# Schaltplan1.net
KiCad netlist of a schematic drawn in EAGLE
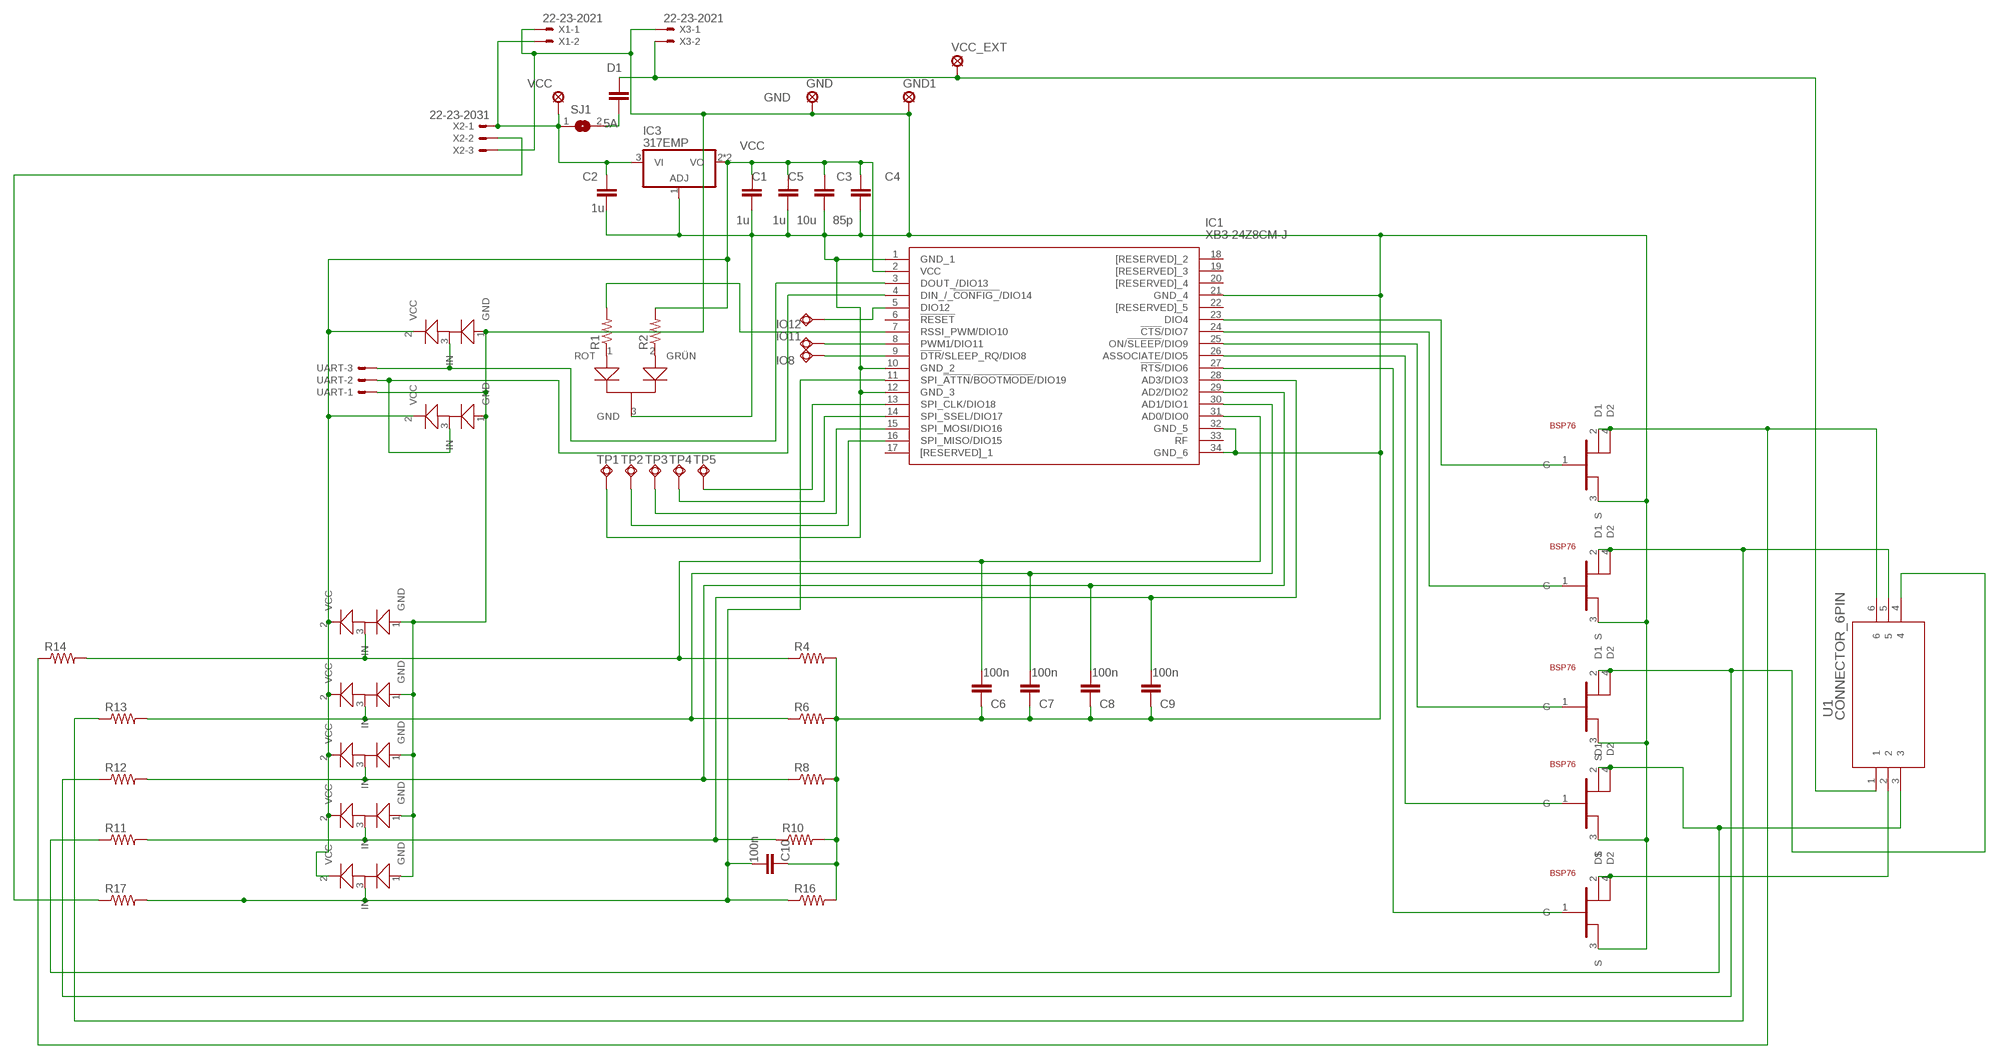
[diagram p0: schematic, sheet 1]

(export (version "E")
  (design (tool "Eeschema 10.0.6"))
  (components
    (comp (ref "C1")
      (value "1u")
      (footprint "eagle-import:CAP_0805")
      (fields
        (field (name "DIGIKEY_PART_NUMBER") "311-1140-2-ND")
        (field (name "MANUFACTURER") "Yageo")
        (field (name "MPN") "CC0805KRX7R9BB104")
        (field (name "CREATED_BY") "PCBLayout.com")
      )
      (libsource (lib "eagle-import") (part "CC0805KRX7R9BB104"))
    )
    (comp (ref "C2")
      (value "1u")
      (footprint "eagle-import:CAP_0805")
      (fields
        (field (name "DIGIKEY_PART_NUMBER") "311-1140-2-ND")
        (field (name "MANUFACTURER") "Yageo")
        (field (name "MPN") "CC0805KRX7R9BB104")
        (field (name "CREATED_BY") "PCBLayout.com")
      )
      (libsource (lib "eagle-import") (part "CC0805KRX7R9BB104"))
    )
    (comp (ref "C3")
      (value "10u")
      (footprint "eagle-import:CAP_0805")
      (fields
        (field (name "DIGIKEY_PART_NUMBER") "311-1140-2-ND")
        (field (name "MANUFACTURER") "Yageo")
        (field (name "MPN") "CC0805KRX7R9BB104")
        (field (name "CREATED_BY") "PCBLayout.com")
      )
      (libsource (lib "eagle-import") (part "CC0805KRX7R9BB104"))
    )
    (comp (ref "C4")
      (value "85p")
      (footprint "eagle-import:CAP_0805")
      (fields
        (field (name "DIGIKEY_PART_NUMBER") "311-1140-2-ND")
        (field (name "MANUFACTURER") "Yageo")
        (field (name "MPN") "CC0805KRX7R9BB104")
        (field (name "CREATED_BY") "PCBLayout.com")
      )
      (libsource (lib "eagle-import") (part "CC0805KRX7R9BB104"))
    )
    (comp (ref "C5")
      (value "1u")
      (footprint "eagle-import:CAP_0805")
      (fields
        (field (name "DIGIKEY_PART_NUMBER") "311-1140-2-ND")
        (field (name "MANUFACTURER") "Yageo")
        (field (name "MPN") "CC0805KRX7R9BB104")
        (field (name "CREATED_BY") "PCBLayout.com")
      )
      (libsource (lib "eagle-import") (part "CC0805KRX7R9BB104"))
    )
    (comp (ref "C6")
      (value "100n")
      (footprint "eagle-import:CAP_0805")
      (fields
        (field (name "DIGIKEY_PART_NUMBER") "311-1140-2-ND")
        (field (name "MANUFACTURER") "Yageo")
        (field (name "MPN") "CC0805KRX7R9BB104")
        (field (name "CREATED_BY") "PCBLayout.com")
      )
      (libsource (lib "eagle-import") (part "CC0805KRX7R9BB104"))
    )
    (comp (ref "C7")
      (value "100n")
      (footprint "eagle-import:CAP_0805")
      (fields
        (field (name "DIGIKEY_PART_NUMBER") "311-1140-2-ND")
        (field (name "MANUFACTURER") "Yageo")
        (field (name "MPN") "CC0805KRX7R9BB104")
        (field (name "CREATED_BY") "PCBLayout.com")
      )
      (libsource (lib "eagle-import") (part "CC0805KRX7R9BB104"))
    )
    (comp (ref "C8")
      (value "100n")
      (footprint "eagle-import:CAP_0805")
      (fields
        (field (name "DIGIKEY_PART_NUMBER") "311-1140-2-ND")
        (field (name "MANUFACTURER") "Yageo")
        (field (name "MPN") "CC0805KRX7R9BB104")
        (field (name "CREATED_BY") "PCBLayout.com")
      )
      (libsource (lib "eagle-import") (part "CC0805KRX7R9BB104"))
    )
    (comp (ref "C9")
      (value "100n")
      (footprint "eagle-import:CAP_0805")
      (fields
        (field (name "DIGIKEY_PART_NUMBER") "311-1140-2-ND")
        (field (name "MANUFACTURER") "Yageo")
        (field (name "MPN") "CC0805KRX7R9BB104")
        (field (name "CREATED_BY") "PCBLayout.com")
      )
      (libsource (lib "eagle-import") (part "CC0805KRX7R9BB104"))
    )
    (comp (ref "C10")
      (value "100n")
      (footprint "eagle-import:CAP_0805")
      (fields
        (field (name "DIGIKEY_PART_NUMBER") "311-1140-2-ND")
        (field (name "MANUFACTURER") "Yageo")
        (field (name "MPN") "CC0805KRX7R9BB104")
        (field (name "CREATED_BY") "PCBLayout.com")
      )
      (libsource (lib "eagle-import") (part "CC0805KRX7R9BB104"))
    )
    (comp (ref "D1")
      (value "5A")
      (footprint "eagle-import:CAP_0805")
      (fields
        (field (name "DIGIKEY_PART_NUMBER") "311-1140-2-ND")
        (field (name "MANUFACTURER") "Yageo")
        (field (name "MPN") "CC0805KRX7R9BB104")
        (field (name "CREATED_BY") "PCBLayout.com")
      )
      (libsource (lib "eagle-import") (part "CC0805KRX7R9BB104"))
    )
    (comp (ref "GND")
      (value "LSP10")
      (footprint "eagle-import:LSP10")
      (libsource (lib "eagle-import") (part "LSP10"))
    )
    (comp (ref "GND1")
      (value "LSP10")
      (footprint "eagle-import:LSP10")
      (libsource (lib "eagle-import") (part "LSP10"))
    )
    (comp (ref "IC1")
      (value "XB3-24Z8CM-J")
      (footprint "eagle-import:XB324Z8CMJ")
      (fields (field (name "MOUSER_PART_NUMBER") "888-XB3-24Z8CM-J"))
      (libsource (lib "eagle-import") (part "XB3-24Z8CM-J"))
    )
    (comp (ref "IC3")
      (value "317EMP")
      (footprint "eagle-import:SOT223")
      (libsource (lib "eagle-import") (part "317EMP"))
    )
    (comp (ref "IO8")
      (value "TPSQB1,27")
      (footprint "eagle-import:B1,27")
      (libsource (lib "eagle-import") (part "TPSQB1,27"))
    )
    (comp (ref "IO11")
      (value "TPSQB1,27")
      (footprint "eagle-import:B1,27")
      (libsource (lib "eagle-import") (part "TPSQB1,27"))
    )
    (comp (ref "IO12")
      (value "TPSQB1,27")
      (footprint "eagle-import:B1,27")
      (libsource (lib "eagle-import") (part "TPSQB1,27"))
    )
    (comp (ref "LED")
      (value "LED_RG_SOT23")
      (footprint "eagle-import:SOT23")
      (libsource (lib "eagle-import") (part "LED_RG_SOT23"))
    )
    (comp (ref "R1")
      (value "150")
      (footprint "eagle-import:RES_0805")
      (fields
        (field (name "DIGIKEY_PART_NUMBER") "541-0.0ATR-ND")
        (field (name "MANUFACTURER") "Vishay Dale")
        (field (name "MPN") "CRCW08050000Z0EA")
        (field (name "CREATED_BY") "PCBLayout.com")
      )
      (libsource (lib "eagle-import") (part "CRCW08050000Z0EA"))
    )
    (comp (ref "R2")
      (value "CRCW08050000Z0EA")
      (footprint "eagle-import:RES_0805")
      (fields
        (field (name "DIGIKEY_PART_NUMBER") "541-0.0ATR-ND")
        (field (name "MANUFACTURER") "Vishay Dale")
        (field (name "CREATED_BY") "PCBLayout.com")
      )
      (libsource (lib "eagle-import") (part "CRCW08050000Z0EA"))
    )
    (comp (ref "R4")
      (value "47k")
      (footprint "eagle-import:RES_0805")
      (fields
        (field (name "DIGIKEY_PART_NUMBER") "541-0.0ATR-ND")
        (field (name "MANUFACTURER") "Vishay Dale")
        (field (name "MPN") "CRCW08050000Z0EA")
        (field (name "CREATED_BY") "PCBLayout.com")
      )
      (libsource (lib "eagle-import") (part "CRCW08050000Z0EA"))
    )
    (comp (ref "R6")
      (value "CRCW08050000Z0EA")
      (footprint "eagle-import:RES_0805")
      (fields
        (field (name "DIGIKEY_PART_NUMBER") "541-0.0ATR-ND")
        (field (name "MANUFACTURER") "Vishay Dale")
        (field (name "CREATED_BY") "PCBLayout.com")
      )
      (libsource (lib "eagle-import") (part "CRCW08050000Z0EA"))
    )
    (comp (ref "R8")
      (value "CRCW08050000Z0EA")
      (footprint "eagle-import:RES_0805")
      (fields
        (field (name "DIGIKEY_PART_NUMBER") "541-0.0ATR-ND")
        (field (name "MANUFACTURER") "Vishay Dale")
        (field (name "CREATED_BY") "PCBLayout.com")
      )
      (libsource (lib "eagle-import") (part "CRCW08050000Z0EA"))
    )
    (comp (ref "R10")
      (value "CRCW08050000Z0EA")
      (footprint "eagle-import:RES_0805")
      (fields
        (field (name "DIGIKEY_PART_NUMBER") "541-0.0ATR-ND")
        (field (name "MANUFACTURER") "Vishay Dale")
        (field (name "CREATED_BY") "PCBLayout.com")
      )
      (libsource (lib "eagle-import") (part "CRCW08050000Z0EA"))
    )
    (comp (ref "R11")
      (value "CRCW08050000Z0EA")
      (footprint "eagle-import:RES_0805")
      (fields
        (field (name "DIGIKEY_PART_NUMBER") "541-0.0ATR-ND")
        (field (name "MANUFACTURER") "Vishay Dale")
        (field (name "CREATED_BY") "PCBLayout.com")
      )
      (libsource (lib "eagle-import") (part "CRCW08050000Z0EA"))
    )
    (comp (ref "R12")
      (value "CRCW08050000Z0EA")
      (footprint "eagle-import:RES_0805")
      (fields
        (field (name "DIGIKEY_PART_NUMBER") "541-0.0ATR-ND")
        (field (name "MANUFACTURER") "Vishay Dale")
        (field (name "CREATED_BY") "PCBLayout.com")
      )
      (libsource (lib "eagle-import") (part "CRCW08050000Z0EA"))
    )
    (comp (ref "R13")
      (value "CRCW08050000Z0EA")
      (footprint "eagle-import:RES_0805")
      (fields
        (field (name "DIGIKEY_PART_NUMBER") "541-0.0ATR-ND")
        (field (name "MANUFACTURER") "Vishay Dale")
        (field (name "CREATED_BY") "PCBLayout.com")
      )
      (libsource (lib "eagle-import") (part "CRCW08050000Z0EA"))
    )
    (comp (ref "R14")
      (value "CRCW08050000Z0EA")
      (footprint "eagle-import:RES_0805")
      (fields
        (field (name "DIGIKEY_PART_NUMBER") "541-0.0ATR-ND")
        (field (name "MANUFACTURER") "Vishay Dale")
        (field (name "CREATED_BY") "PCBLayout.com")
      )
      (libsource (lib "eagle-import") (part "CRCW08050000Z0EA"))
    )
    (comp (ref "R16")
      (value "CRCW08050000Z0EA")
      (footprint "eagle-import:RES_0805")
      (fields
        (field (name "DIGIKEY_PART_NUMBER") "541-0.0ATR-ND")
        (field (name "MANUFACTURER") "Vishay Dale")
        (field (name "CREATED_BY") "PCBLayout.com")
      )
      (libsource (lib "eagle-import") (part "CRCW08050000Z0EA"))
    )
    (comp (ref "R17")
      (value "CRCW08050000Z0EA")
      (footprint "eagle-import:RES_0805")
      (fields
        (field (name "DIGIKEY_PART_NUMBER") "541-0.0ATR-ND")
        (field (name "MANUFACTURER") "Vishay Dale")
        (field (name "CREATED_BY") "PCBLayout.com")
      )
      (libsource (lib "eagle-import") (part "CRCW08050000Z0EA"))
    )
    (comp (ref "SJ1")
      (value "SJW")
      (footprint "eagle-import:SJW")
      (libsource (lib "eagle-import") (part "SJW"))
    )
    (comp (ref "TP1")
      (value "TPSQB1,27")
      (footprint "eagle-import:B1,27")
      (libsource (lib "eagle-import") (part "TPSQB1,27"))
    )
    (comp (ref "TP2")
      (value "TPSQB1,27")
      (footprint "eagle-import:B1,27")
      (libsource (lib "eagle-import") (part "TPSQB1,27"))
    )
    (comp (ref "TP3")
      (value "TPSQB1,27")
      (footprint "eagle-import:B1,27")
      (libsource (lib "eagle-import") (part "TPSQB1,27"))
    )
    (comp (ref "TP4")
      (value "TPSQB1,27")
      (footprint "eagle-import:B1,27")
      (libsource (lib "eagle-import") (part "TPSQB1,27"))
    )
    (comp (ref "TP5")
      (value "TPSQB1,27")
      (footprint "eagle-import:B1,27")
      (libsource (lib "eagle-import") (part "TPSQB1,27"))
    )
    (comp (ref "U$1")
      (value "BSP76")
      (footprint "eagle-import:SOT223")
      (libsource (lib "eagle-import") (part "BSP76"))
    )
    (comp (ref "U$2")
      (value "BSP76")
      (footprint "eagle-import:SOT223")
      (libsource (lib "eagle-import") (part "BSP76"))
    )
    (comp (ref "U$3")
      (value "BSP76")
      (footprint "eagle-import:SOT223")
      (libsource (lib "eagle-import") (part "BSP76"))
    )
    (comp (ref "U$4")
      (value "BSP76")
      (footprint "eagle-import:SOT223")
      (libsource (lib "eagle-import") (part "BSP76"))
    )
    (comp (ref "U$5")
      (value "BSP76")
      (footprint "eagle-import:SOT223")
      (libsource (lib "eagle-import") (part "BSP76"))
    )
    (comp (ref "U$6")
      (value "TVS-DIODE")
      (footprint "eagle-import:SOT23-R")
      (libsource (lib "eagle-import") (part "TVS-DIODE"))
    )
    (comp (ref "U$7")
      (value "TVS-DIODE")
      (footprint "eagle-import:SOT23-R")
      (libsource (lib "eagle-import") (part "TVS-DIODE"))
    )
    (comp (ref "U$8")
      (value "TVS-DIODE")
      (footprint "eagle-import:SOT23-R")
      (libsource (lib "eagle-import") (part "TVS-DIODE"))
    )
    (comp (ref "U$9")
      (value "TVS-DIODE")
      (footprint "eagle-import:SOT23-R")
      (libsource (lib "eagle-import") (part "TVS-DIODE"))
    )
    (comp (ref "U$10")
      (value "TVS-DIODE")
      (footprint "eagle-import:SOT23-R")
      (libsource (lib "eagle-import") (part "TVS-DIODE"))
    )
    (comp (ref "U$11")
      (value "TVS-DIODE")
      (footprint "eagle-import:SOT23-R")
      (libsource (lib "eagle-import") (part "TVS-DIODE"))
    )
    (comp (ref "U$12")
      (value "TVS-DIODE")
      (footprint "eagle-import:SOT23-R")
      (libsource (lib "eagle-import") (part "TVS-DIODE"))
    )
    (comp (ref "U1")
      (value "CONNECTOR_6PIN")
      (footprint "eagle-import:282836-6")
      (fields (field (name "MANUFACTURER_PART_NUMBER") "2828366"))
      (libsource (lib "eagle-import") (part "CONNECTOR_6PIN"))
    )
    (comp (ref "UART")
      (value "22-23-2031")
      (footprint "eagle-import:22-23-2031")
      (fields (field (name "MF") "MOLEX"))
      (libsource (lib "eagle-import") (part "22-23-2031"))
    )
    (comp (ref "VCC")
      (value "LSP10")
      (footprint "eagle-import:LSP10")
      (libsource (lib "eagle-import") (part "LSP10"))
    )
    (comp (ref "VCC_EXT")
      (value "LSP10")
      (footprint "eagle-import:LSP10")
      (libsource (lib "eagle-import") (part "LSP10"))
    )
    (comp (ref "X1")
      (value "22-23-2021")
      (footprint "eagle-import:22-23-2021")
      (fields (field (name "MF") "MOLEX"))
      (libsource (lib "eagle-import") (part "22-23-2021"))
    )
    (comp (ref "X2")
      (value "22-23-2031")
      (footprint "eagle-import:22-23-2031")
      (fields (field (name "MF") "MOLEX"))
      (libsource (lib "eagle-import") (part "22-23-2031"))
    )
    (comp (ref "X3")
      (value "22-23-2021")
      (footprint "eagle-import:22-23-2021")
      (fields (field (name "MF") "MOLEX"))
      (libsource (lib "eagle-import") (part "22-23-2021"))
    )
  )
  (nets
    (net (code "1") (name "/GND") (class "Default")
      (node (ref "C1") (pin "2") (pinfunction "2_2") (pintype "passive"))
      (node (ref "C10") (pin "1") (pinfunction "1_1") (pintype "passive"))
      (node (ref "C2") (pin "2") (pinfunction "2_2") (pintype "passive"))
      (node (ref "C3") (pin "1") (pinfunction "1_1") (pintype "passive"))
      (node (ref "C4") (pin "1") (pinfunction "1_1") (pintype "passive"))
      (node (ref "C5") (pin "2") (pinfunction "2_2") (pintype "passive"))
      (node (ref "C6") (pin "1") (pinfunction "1_1") (pintype "passive"))
      (node (ref "C7") (pin "1") (pinfunction "1_1") (pintype "passive"))
      (node (ref "C8") (pin "1") (pinfunction "1_1") (pintype "passive"))
      (node (ref "C9") (pin "1") (pinfunction "1_1") (pintype "passive"))
      (node (ref "GND") (pin "MP") (pinfunction "MP_MP") (pintype "passive"))
      (node (ref "GND1") (pin "MP") (pinfunction "MP_MP") (pintype "passive"))
      (node (ref "IC1") (pin "1") (pinfunction "GND_1_1") (pintype "bidirectional"))
      (node (ref "IC1") (pin "10") (pinfunction "GND_2_10") (pintype "bidirectional"))
      (node (ref "IC1") (pin "12") (pinfunction "GND_3_12") (pintype "bidirectional"))
      (node (ref "IC1") (pin "21") (pinfunction "GND_4_21") (pintype "bidirectional"))
      (node (ref "IC1") (pin "32") (pinfunction "GND_5_32") (pintype "bidirectional"))
      (node (ref "IC1") (pin "34") (pinfunction "GND_6_34") (pintype "bidirectional"))
      (node (ref "IC3") (pin "1") (pinfunction "ADJ_1") (pintype "input"))
      (node (ref "LED") (pin "3") (pinfunction "GND_3") (pintype "bidirectional"))
      (node (ref "R10") (pin "2") (pinfunction "2_2") (pintype "passive"))
      (node (ref "R16") (pin "2") (pinfunction "2_2") (pintype "passive"))
      (node (ref "R4") (pin "2") (pinfunction "2_2") (pintype "passive"))
      (node (ref "R6") (pin "2") (pinfunction "2_2") (pintype "passive"))
      (node (ref "R8") (pin "2") (pinfunction "2_2") (pintype "passive"))
      (node (ref "TP1") (pin "TP") (pinfunction "TP_TP") (pintype "input"))
      (node (ref "U$1") (pin "3") (pinfunction "S_3") (pintype "bidirectional"))
      (node (ref "U$10") (pin "1") (pinfunction "GND_1") (pintype "bidirectional"))
      (node (ref "U$11") (pin "1") (pinfunction "GND_1") (pintype "bidirectional"))
      (node (ref "U$12") (pin "1") (pinfunction "GND_1") (pintype "bidirectional"))
      (node (ref "U$2") (pin "3") (pinfunction "S_3") (pintype "bidirectional"))
      (node (ref "U$3") (pin "3") (pinfunction "S_3") (pintype "bidirectional"))
      (node (ref "U$4") (pin "3") (pinfunction "S_3") (pintype "bidirectional"))
      (node (ref "U$5") (pin "3") (pinfunction "S_3") (pintype "bidirectional"))
      (node (ref "U$6") (pin "1") (pinfunction "GND_1") (pintype "bidirectional"))
      (node (ref "U$7") (pin "1") (pinfunction "GND_1") (pintype "bidirectional"))
      (node (ref "U$8") (pin "1") (pinfunction "GND_1") (pintype "bidirectional"))
      (node (ref "U$9") (pin "1") (pinfunction "GND_1") (pintype "bidirectional"))
      (node (ref "UART") (pin "1") (pinfunction "S_1") (pintype "passive"))
      (node (ref "X1") (pin "1") (pinfunction "S_1") (pintype "passive"))
      (node (ref "X2") (pin "3") (pinfunction "S_3") (pintype "passive"))
      (node (ref "X3") (pin "1") (pinfunction "S_1") (pintype "passive"))
    )
    (net (code "2") (name "/VCC") (class "Default")
      (node (ref "C1") (pin "1") (pinfunction "1_1") (pintype "passive"))
      (node (ref "C3") (pin "2") (pinfunction "2_2") (pintype "passive"))
      (node (ref "C4") (pin "2") (pinfunction "2_2") (pintype "passive"))
      (node (ref "C5") (pin "1") (pinfunction "1_1") (pintype "passive"))
      (node (ref "IC1") (pin "2") (pinfunction "VCC_2") (pintype "bidirectional"))
      (node (ref "IC3") (pin "2") (pinfunction "VO_2") (pintype "passive"))
      (node (ref "IC3") (pin "4") (pinfunction "VO_4") (pintype "passive"))
      (node (ref "R2") (pin "2") (pinfunction "2_2") (pintype "passive"))
      (node (ref "U$10") (pin "2") (pinfunction "VCC_2") (pintype "power_in"))
      (node (ref "U$11") (pin "2") (pinfunction "VCC_2") (pintype "power_in"))
      (node (ref "U$12") (pin "2") (pinfunction "VCC_2") (pintype "power_in"))
      (node (ref "U$6") (pin "2") (pinfunction "VCC_2") (pintype "power_in"))
      (node (ref "U$7") (pin "2") (pinfunction "VCC_2") (pintype "power_in"))
      (node (ref "U$8") (pin "2") (pinfunction "VCC_2") (pintype "power_in"))
      (node (ref "U$9") (pin "2") (pinfunction "VCC_2") (pintype "power_in"))
    )
    (net (code "3") (name "Net-(D1-Pad2)") (class "Default")
      (node (ref "D1") (pin "2") (pinfunction "2_2") (pintype "passive"))
      (node (ref "SJ1") (pin "2") (pinfunction "2_2") (pintype "passive"))
    )
    (net (code "4") (name "Net-(IC1-AD0{slash}DIO0)") (class "Default")
      (node (ref "C6") (pin "2") (pinfunction "2_2") (pintype "passive"))
      (node (ref "IC1") (pin "31") (pinfunction "AD0/DIO0_31") (pintype "bidirectional"))
      (node (ref "R14") (pin "2") (pinfunction "2_2") (pintype "passive"))
      (node (ref "R4") (pin "1") (pinfunction "1_1") (pintype "passive"))
      (node (ref "U$7") (pin "3") (pinfunction "IN_3") (pintype "bidirectional"))
    )
    (net (code "5") (name "Net-(IC1-AD1{slash}DIO1)") (class "Default")
      (node (ref "C7") (pin "2") (pinfunction "2_2") (pintype "passive"))
      (node (ref "IC1") (pin "30") (pinfunction "AD1/DIO1_30") (pintype "bidirectional"))
      (node (ref "R13") (pin "2") (pinfunction "2_2") (pintype "passive"))
      (node (ref "R6") (pin "1") (pinfunction "1_1") (pintype "passive"))
      (node (ref "U$8") (pin "3") (pinfunction "IN_3") (pintype "bidirectional"))
    )
    (net (code "6") (name "Net-(IC1-AD2{slash}DIO2)") (class "Default")
      (node (ref "C8") (pin "2") (pinfunction "2_2") (pintype "passive"))
      (node (ref "IC1") (pin "29") (pinfunction "AD2/DIO2_29") (pintype "bidirectional"))
      (node (ref "R12") (pin "2") (pinfunction "2_2") (pintype "passive"))
      (node (ref "R8") (pin "1") (pinfunction "1_1") (pintype "passive"))
      (node (ref "U$9") (pin "3") (pinfunction "IN_3") (pintype "bidirectional"))
    )
    (net (code "7") (name "Net-(IC1-AD3{slash}DIO3)") (class "Default")
      (node (ref "C9") (pin "2") (pinfunction "2_2") (pintype "passive"))
      (node (ref "IC1") (pin "28") (pinfunction "AD3/DIO3_28") (pintype "bidirectional"))
      (node (ref "R10") (pin "1") (pinfunction "1_1") (pintype "passive"))
      (node (ref "R11") (pin "2") (pinfunction "2_2") (pintype "passive"))
      (node (ref "U$10") (pin "3") (pinfunction "IN_3") (pintype "bidirectional"))
    )
    (net (code "8") (name "Net-(IC1-ASSOCIATE{slash}DIO5)") (class "Default")
      (node (ref "IC1") (pin "26") (pinfunction "ASSOCIATE/DIO5_26") (pintype "bidirectional"))
      (node (ref "U$4") (pin "1") (pinfunction "G_1") (pintype "input"))
    )
    (net (code "9") (name "Net-(IC1-DIN_{slash}_~{CONFIG_}{slash}DIO14)") (class "Default")
      (node (ref "IC1") (pin "4") (pinfunction "DIN_/_~{CONFIG_}/DIO14_4") (pintype "bidirectional"))
      (node (ref "U$12") (pin "3") (pinfunction "IN_3") (pintype "bidirectional"))
      (node (ref "UART") (pin "2") (pinfunction "S_2") (pintype "passive"))
    )
    (net (code "10") (name "Net-(IC1-DIO4)") (class "Default")
      (node (ref "IC1") (pin "23") (pinfunction "DIO4_23") (pintype "bidirectional"))
      (node (ref "U$1") (pin "1") (pinfunction "G_1") (pintype "input"))
    )
    (net (code "11") (name "Net-(IC1-DIO12)") (class "Default")
      (node (ref "IC1") (pin "5") (pinfunction "DIO12_5") (pintype "bidirectional"))
      (node (ref "IO12") (pin "TP") (pinfunction "TP_TP") (pintype "input"))
    )
    (net (code "12") (name "Net-(IC1-DOUT_{slash}DIO13)") (class "Default")
      (node (ref "IC1") (pin "3") (pinfunction "DOUT_/DIO13_3") (pintype "bidirectional"))
      (node (ref "U$11") (pin "3") (pinfunction "IN_3") (pintype "bidirectional"))
      (node (ref "UART") (pin "3") (pinfunction "S_3") (pintype "passive"))
    )
    (net (code "13") (name "Net-(IC1-ON{slash}~{SLEEP}{slash}DIO9)") (class "Default")
      (node (ref "IC1") (pin "25") (pinfunction "ON/~{SLEEP}/DIO9_25") (pintype "bidirectional"))
      (node (ref "U$3") (pin "1") (pinfunction "G_1") (pintype "input"))
    )
    (net (code "14") (name "Net-(IC1-PWM1{slash}DIO11)") (class "Default")
      (node (ref "IC1") (pin "8") (pinfunction "PWM1/DIO11_8") (pintype "bidirectional"))
      (node (ref "IO11") (pin "TP") (pinfunction "TP_TP") (pintype "input"))
    )
    (net (code "15") (name "Net-(IC1-RSSI_PWM{slash}DIO10)") (class "Default")
      (node (ref "IC1") (pin "7") (pinfunction "RSSI_PWM/DIO10_7") (pintype "bidirectional"))
      (node (ref "R1") (pin "2") (pinfunction "2_2") (pintype "passive"))
    )
    (net (code "16") (name "Net-(IC1-SPI_CLK{slash}DIO18)") (class "Default")
      (node (ref "IC1") (pin "13") (pinfunction "SPI_CLK/DIO18_13") (pintype "bidirectional"))
      (node (ref "TP5") (pin "TP") (pinfunction "TP_TP") (pintype "input"))
    )
    (net (code "17") (name "Net-(IC1-SPI_MISO{slash}DIO15)") (class "Default")
      (node (ref "IC1") (pin "16") (pinfunction "SPI_MISO/DIO15_16") (pintype "bidirectional"))
      (node (ref "TP2") (pin "TP") (pinfunction "TP_TP") (pintype "input"))
    )
    (net (code "18") (name "Net-(IC1-SPI_MOSI{slash}DIO16)") (class "Default")
      (node (ref "IC1") (pin "15") (pinfunction "SPI_MOSI/DIO16_15") (pintype "bidirectional"))
      (node (ref "TP3") (pin "TP") (pinfunction "TP_TP") (pintype "input"))
    )
    (net (code "19") (name "Net-(IC1-SPI_SSEL{slash}DIO17)") (class "Default")
      (node (ref "IC1") (pin "14") (pinfunction "SPI_SSEL/DIO17_14") (pintype "bidirectional"))
      (node (ref "TP4") (pin "TP") (pinfunction "TP_TP") (pintype "input"))
    )
    (net (code "20") (name "Net-(IC1-SPI_~{ATTN}{slash}~{BOOTMODE}{slash}DIO19)") (class "Default")
      (node (ref "C10") (pin "2") (pinfunction "2_2") (pintype "passive"))
      (node (ref "IC1") (pin "11") (pinfunction "SPI_~{ATTN}/~{BOOTMODE}/DIO19_11") (pintype "bidirectional"))
      (node (ref "R16") (pin "1") (pinfunction "1_1") (pintype "passive"))
      (node (ref "R17") (pin "2") (pinfunction "2_2") (pintype "passive"))
      (node (ref "U$6") (pin "3") (pinfunction "IN_3") (pintype "bidirectional"))
    )
    (net (code "21") (name "Net-(IC1-~{CTS}{slash}DIO7)") (class "Default")
      (node (ref "IC1") (pin "24") (pinfunction "~{CTS}/DIO7_24") (pintype "bidirectional"))
      (node (ref "U$2") (pin "1") (pinfunction "G_1") (pintype "input"))
    )
    (net (code "22") (name "Net-(IC1-~{DTR}{slash}SLEEP_RQ{slash}DIO8)") (class "Default")
      (node (ref "IC1") (pin "9") (pinfunction "~{DTR}/SLEEP_RQ/DIO8_9") (pintype "bidirectional"))
      (node (ref "IO8") (pin "TP") (pinfunction "TP_TP") (pintype "input"))
    )
    (net (code "23") (name "Net-(IC1-~{RTS}{slash}DIO6)") (class "Default")
      (node (ref "IC1") (pin "27") (pinfunction "~{RTS}/DIO6_27") (pintype "bidirectional"))
      (node (ref "U$5") (pin "1") (pinfunction "G_1") (pintype "input"))
    )
    (net (code "24") (name "Net-(IC3-VI)") (class "Default")
      (node (ref "C2") (pin "1") (pinfunction "1_1") (pintype "passive"))
      (node (ref "IC3") (pin "3") (pinfunction "VI_3") (pintype "input"))
      (node (ref "SJ1") (pin "1") (pinfunction "1_1") (pintype "passive"))
      (node (ref "VCC") (pin "MP") (pinfunction "MP_MP") (pintype "passive"))
      (node (ref "X1") (pin "2") (pinfunction "S_2") (pintype "passive"))
      (node (ref "X2") (pin "1") (pinfunction "S_1") (pintype "passive"))
    )
    (net (code "25") (name "Net-(LED-GRÜN)") (class "Default")
      (node (ref "LED") (pin "2") (pinfunction "GRÜN_2") (pintype "bidirectional"))
      (node (ref "R2") (pin "1") (pinfunction "1_1") (pintype "passive"))
    )
    (net (code "26") (name "Net-(LED-ROT)") (class "Default")
      (node (ref "LED") (pin "1") (pinfunction "ROT_1") (pintype "bidirectional"))
      (node (ref "R1") (pin "1") (pinfunction "1_1") (pintype "passive"))
    )
    (net (code "27") (name "Net-(U$1-D1)") (class "Default")
      (node (ref "R14") (pin "1") (pinfunction "1_1") (pintype "passive"))
      (node (ref "U$1") (pin "2") (pinfunction "D1_2") (pintype "output"))
      (node (ref "U$1") (pin "4") (pinfunction "D2_4") (pintype "output"))
      (node (ref "U1") (pin "6") (pinfunction "6_6") (pintype "passive"))
    )
    (net (code "28") (name "Net-(U$2-D1)") (class "Default")
      (node (ref "R13") (pin "1") (pinfunction "1_1") (pintype "passive"))
      (node (ref "U$2") (pin "2") (pinfunction "D1_2") (pintype "output"))
      (node (ref "U$2") (pin "4") (pinfunction "D2_4") (pintype "output"))
      (node (ref "U1") (pin "5") (pinfunction "5_5") (pintype "passive"))
    )
    (net (code "29") (name "Net-(U$3-D1)") (class "Default")
      (node (ref "R12") (pin "1") (pinfunction "1_1") (pintype "passive"))
      (node (ref "U$3") (pin "2") (pinfunction "D1_2") (pintype "output"))
      (node (ref "U$3") (pin "4") (pinfunction "D2_4") (pintype "output"))
      (node (ref "U1") (pin "4") (pinfunction "4_4") (pintype "passive"))
    )
    (net (code "30") (name "Net-(U$4-D1)") (class "Default")
      (node (ref "R11") (pin "1") (pinfunction "1_1") (pintype "passive"))
      (node (ref "U$4") (pin "2") (pinfunction "D1_2") (pintype "output"))
      (node (ref "U$4") (pin "4") (pinfunction "D2_4") (pintype "output"))
      (node (ref "U1") (pin "3") (pinfunction "3_3") (pintype "passive"))
    )
    (net (code "31") (name "Net-(U$5-D1)") (class "Default")
      (node (ref "U$5") (pin "2") (pinfunction "D1_2") (pintype "output"))
      (node (ref "U$5") (pin "4") (pinfunction "D2_4") (pintype "output"))
      (node (ref "U1") (pin "2") (pinfunction "2_2") (pintype "passive"))
    )
    (net (code "32") (name "Net-(X2B-S)") (class "Default")
      (node (ref "R17") (pin "1") (pinfunction "1_1") (pintype "passive"))
      (node (ref "X2") (pin "2") (pinfunction "S_2") (pintype "passive"))
    )
    (net (code "33") (name "Net-(X3B-S)") (class "Default")
      (node (ref "D1") (pin "1") (pinfunction "1_1") (pintype "passive"))
      (node (ref "U1") (pin "1") (pinfunction "1_1") (pintype "passive"))
      (node (ref "VCC_EXT") (pin "MP") (pinfunction "MP_MP") (pintype "passive"))
      (node (ref "X3") (pin "2") (pinfunction "S_2") (pintype "passive"))
    )
    (net (code "34") (name "unconnected-(IC1-RF-Pad33)") (class "Default")
      (node (ref "IC1") (pin "33") (pinfunction "RF_33") (pintype "bidirectional"))
    )
    (net (code "35") (name "unconnected-(IC1-[RESERVED]_1-Pad17)") (class "Default")
      (node (ref "IC1") (pin "17") (pinfunction "[RESERVED]_1_17") (pintype "bidirectional"))
    )
    (net (code "36") (name "unconnected-(IC1-[RESERVED]_2-Pad18)") (class "Default")
      (node (ref "IC1") (pin "18") (pinfunction "[RESERVED]_2_18") (pintype "bidirectional"))
    )
    (net (code "37") (name "unconnected-(IC1-[RESERVED]_3-Pad19)") (class "Default")
      (node (ref "IC1") (pin "19") (pinfunction "[RESERVED]_3_19") (pintype "bidirectional"))
    )
    (net (code "38") (name "unconnected-(IC1-[RESERVED]_4-Pad20)") (class "Default")
      (node (ref "IC1") (pin "20") (pinfunction "[RESERVED]_4_20") (pintype "bidirectional"))
    )
    (net (code "39") (name "unconnected-(IC1-[RESERVED]_5-Pad22)") (class "Default")
      (node (ref "IC1") (pin "22") (pinfunction "[RESERVED]_5_22") (pintype "bidirectional"))
    )
    (net (code "40") (name "unconnected-(IC1-~{RESET}-Pad6)") (class "Default")
      (node (ref "IC1") (pin "6") (pinfunction "~{RESET}_6") (pintype "bidirectional"))
    )
  )
)
